# SAM4S_Piezo_LED.net
KiCad netlist of a schematic drawn in Altium Designer
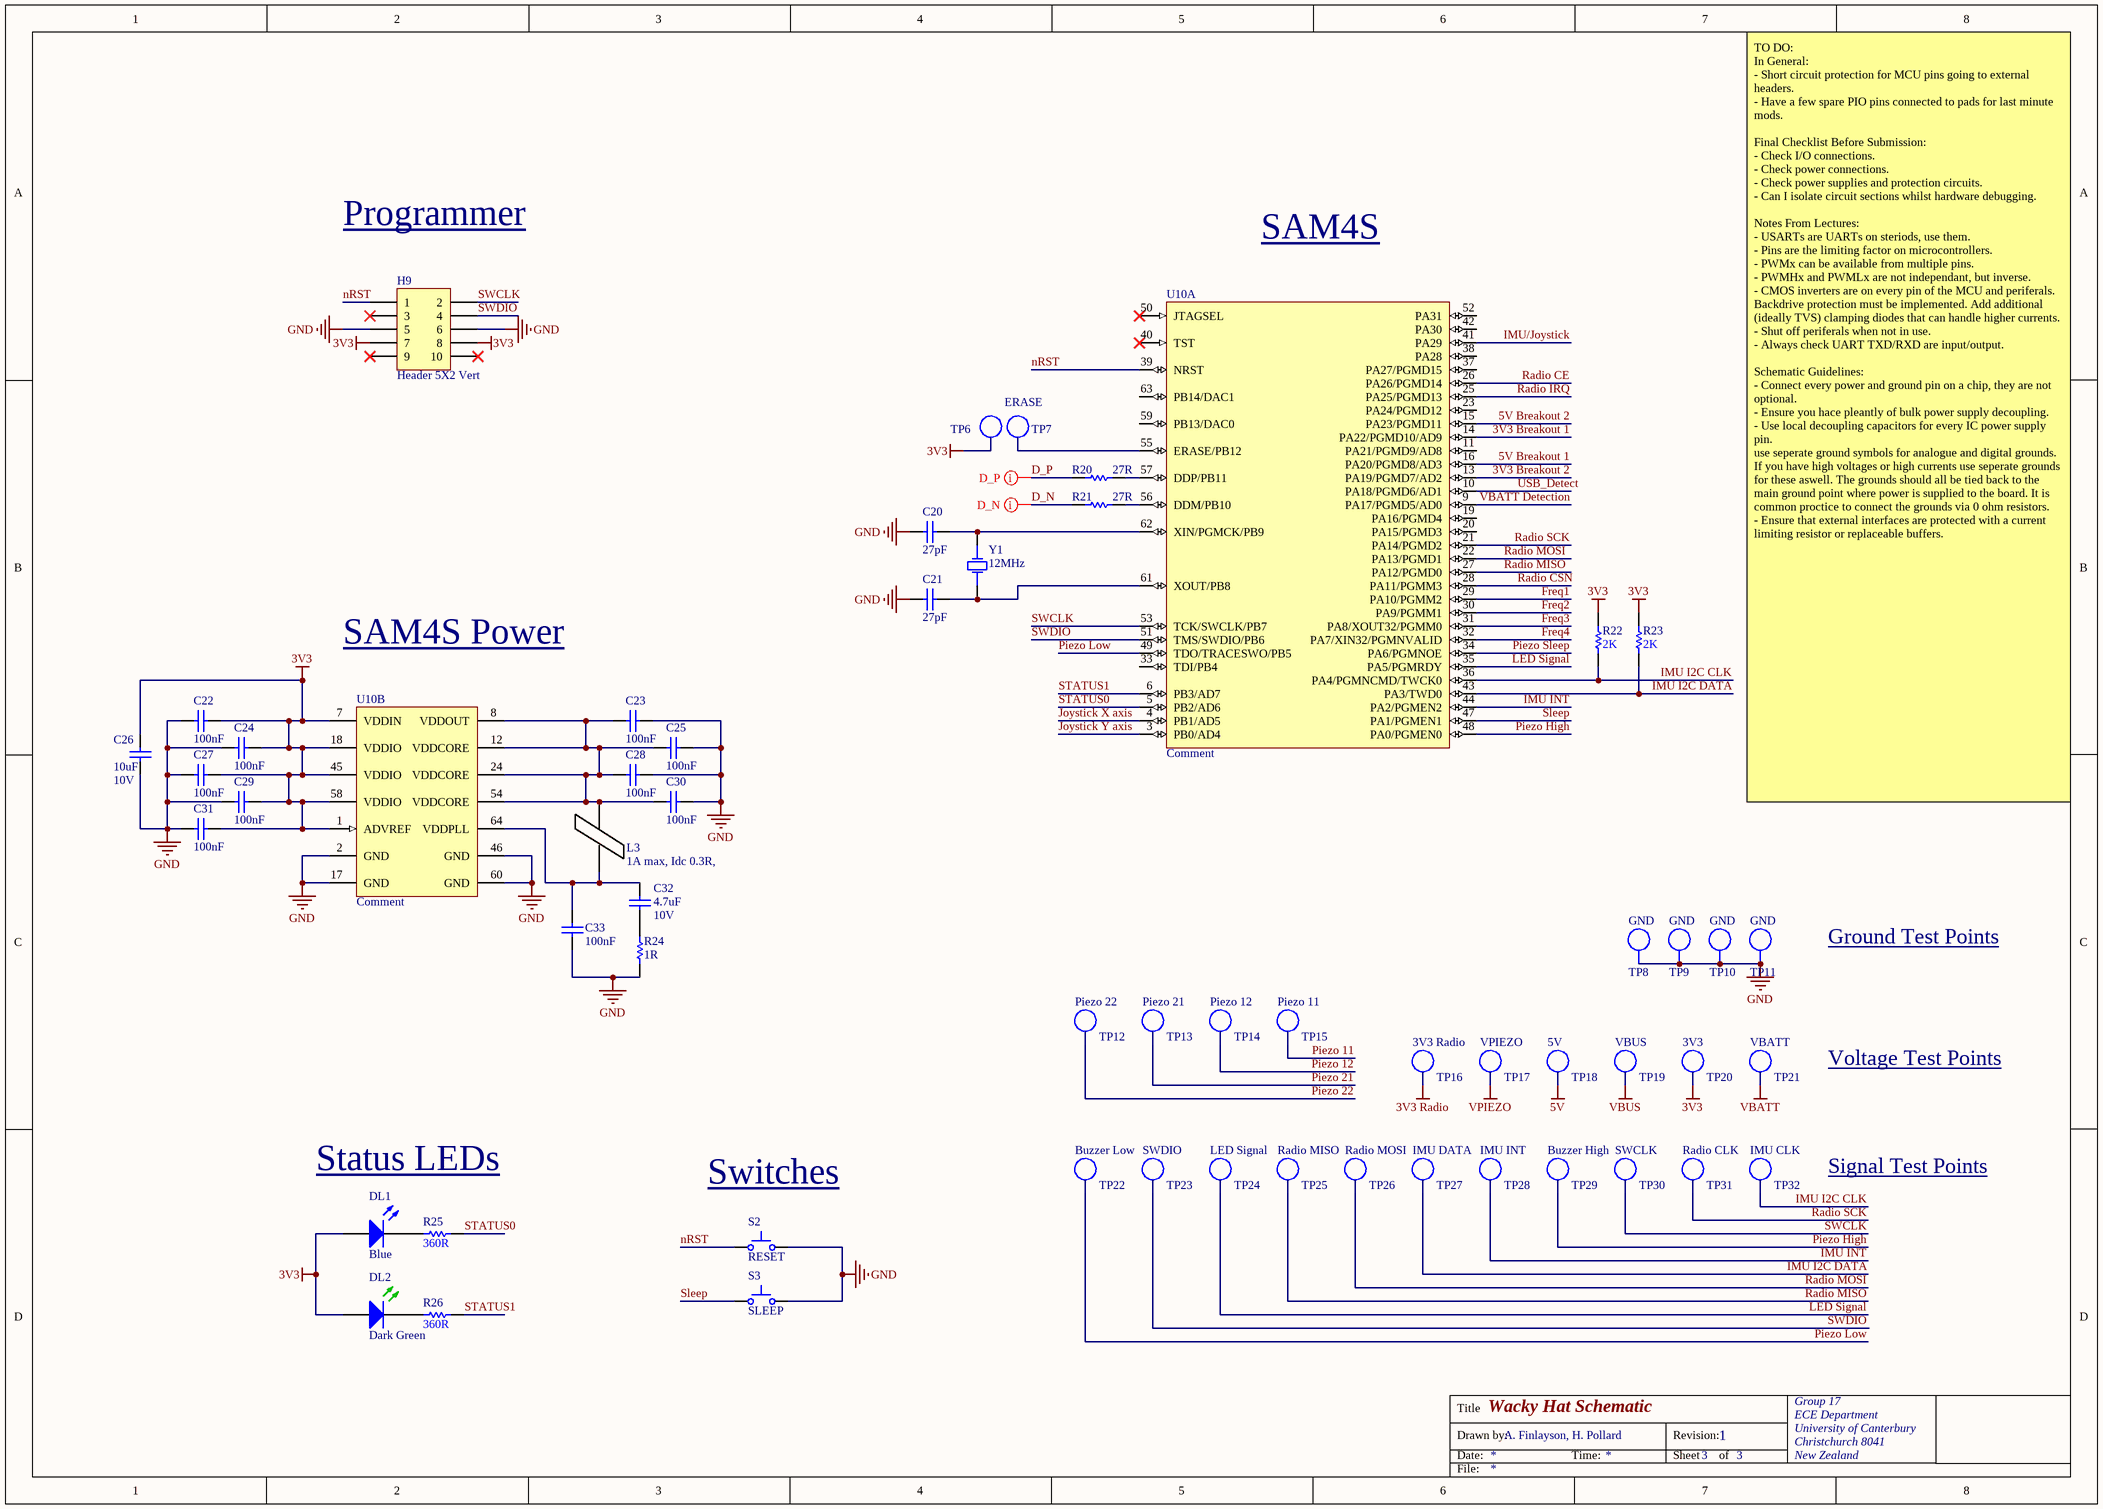
[diagram p0: SAM4S_Piezo_LED.SchDoc]

(export (version "E")
  (design (tool "Eeschema 10.0.6"))
  (components
    (comp (ref "C20")
      (value "27pF")
      (footprint "CAPC1608L")
      (description "CAP CER 27pF NPO/COG +-5% 50V 0603")
      (libsource (lib "ECE AD19Components_19V1") (part "CC_27pF_0603"))
    )
    (comp (ref "C21")
      (value "27pF")
      (footprint "CAPC1608L")
      (description "CAP CER 27pF NPO/COG +-5% 50V 0603")
      (libsource (lib "ECE AD19Components_19V1") (part "CC_27pF_0603"))
    )
    (comp (ref "C22")
      (value "100nF")
      (footprint "CAPC1608L")
      (description "CAP CER 100nF X7R +-10% 50V 0603")
      (libsource (lib "ECE AD19Components_19V1") (part "CC_100nF_0603"))
    )
    (comp (ref "C23")
      (value "100nF")
      (footprint "CAPC1608L")
      (description "CAP CER 100nF X7R +-10% 50V 0603")
      (libsource (lib "ECE AD19Components_19V1") (part "CC_100nF_0603"))
    )
    (comp (ref "C24")
      (value "100nF")
      (footprint "CAPC1608L")
      (description "CAP CER 100nF X7R +-10% 50V 0603")
      (libsource (lib "ECE AD19Components_19V1") (part "CC_100nF_0603"))
    )
    (comp (ref "C25")
      (value "100nF")
      (footprint "CAPC1608L")
      (description "CAP CER 100nF X7R +-10% 50V 0603")
      (libsource (lib "ECE AD19Components_19V1") (part "CC_100nF_0603"))
    )
    (comp (ref "C26")
      (value "10uF")
      (footprint "CAPC2012L")
      (description "CAP CER 10uF X7R +-20% 10V 0805")
      (fields (field (name "MAX VOLTAGE") "10V"))
      (libsource (lib "ECE AD19Components_19V1") (part "CC_10uF_0805_10V"))
    )
    (comp (ref "C27")
      (value "100nF")
      (footprint "CAPC1608L")
      (description "CAP CER 100nF X7R +-10% 50V 0603")
      (libsource (lib "ECE AD19Components_19V1") (part "CC_100nF_0603"))
    )
    (comp (ref "C28")
      (value "100nF")
      (footprint "CAPC1608L")
      (description "CAP CER 100nF X7R +-10% 50V 0603")
      (libsource (lib "ECE AD19Components_19V1") (part "CC_100nF_0603"))
    )
    (comp (ref "C29")
      (value "100nF")
      (footprint "CAPC1608L")
      (description "CAP CER 100nF X7R +-10% 50V 0603")
      (libsource (lib "ECE AD19Components_19V1") (part "CC_100nF_0603"))
    )
    (comp (ref "C30")
      (value "100nF")
      (footprint "CAPC1608L")
      (description "CAP CER 100nF X7R +-10% 50V 0603")
      (libsource (lib "ECE AD19Components_19V1") (part "CC_100nF_0603"))
    )
    (comp (ref "C31")
      (value "100nF")
      (footprint "CAPC1608L")
      (description "CAP CER 100nF X7R +-10% 50V 0603")
      (libsource (lib "ECE AD19Components_19V1") (part "CC_100nF_0603"))
    )
    (comp (ref "C32")
      (value "4.7uF")
      (footprint "CAPC1608N")
      (description "CAP CER 4.7uF X5R +-20%  10V 0603")
      (fields (field (name "MAX VOLTAGE") "10V"))
      (libsource (lib "ECE AD19Components_19V1") (part "CC_4.7uF_0603"))
    )
    (comp (ref "C33")
      (value "100nF")
      (footprint "CAPC1608L")
      (description "CAP CER 100nF X7R +-10% 50V 0603")
      (libsource (lib "ECE AD19Components_19V1") (part "CC_100nF_0603"))
    )
    (comp (ref "DL1")
      (value "Blue")
      (footprint "WL-SMCW0603")
      (description "LED Blue 270mcd 0603 SMD")
      (fields
        (field (name "MANUFACTURER") "WURTH ELEKTRONIK")
        (field (name "MANUFACTURER PART NUMBER") "150060BS75000")
        (field (name "LED COLOUR") "Blue")
      )
      (libsource (lib "ECE AD19Components_19V1") (part "DL_150060BS75000"))
    )
    (comp (ref "DL2")
      (value "Dark Green")
      (footprint "WL-SMCW0603")
      (description "LED Dk Green 430mcd 0603 SMD")
      (fields
        (field (name "MANUFACTURER") "WURTH ELEKTRONIK")
        (field (name "MANUFACTURER PART NUMBER") "150060GS75000")
        (field (name "LED COLOUR") "Dark Green")
      )
      (libsource (lib "ECE AD19Components_19V1") (part "DL_150060GS75000"))
    )
    (comp (ref "H9")
      (value "Header 5X2 Vert")
      (footprint "IDC2.54-V10D")
      (description "IDC Header, 2,54mm, 10-Pin, Vert")
      (libsource (lib "ECE AD19Components_19V1") (part "JA_HDR_IDC_5X2_VERT"))
    )
    (comp (ref "L3")
      (value "1A max, Idc 0.3R,")
      (footprint "INDC3216L")
      (description "Ferrite Bead, Rdc 0.3R, Z100MHZ 600R, Imax 1A, SMD 1206")
      (fields
        (field (name "MANUFACTURER") "FAIR-RITE")
        (field (name "MANUFACTURER PART NUMBER") "2512066017Y1")
      )
      (libsource (lib "ECE AD19Components_19V1") (part "IN_Ferrite-Bead"))
    )
    (comp (ref "R20")
      (value "27R")
      (footprint "RESC1608L")
      (description "RES 27 OHM 1/10W 5% 0603 SMD")
      (libsource (lib "ECE AD19Components_19V1") (part "RS_27R"))
    )
    (comp (ref "R21")
      (value "27R")
      (footprint "RESC1608L")
      (description "RES 27 OHM 1/10W 5% 0603 SMD")
      (libsource (lib "ECE AD19Components_19V1") (part "RS_27R"))
    )
    (comp (ref "R22")
      (value "2K")
      (footprint "RESC1608L")
      (description "RES 2K OHM 1/10W 5% 0603 SMD")
      (libsource (lib "ECE AD19Components_19V1") (part "RS_2K"))
    )
    (comp (ref "R23")
      (value "2K")
      (footprint "RESC1608L")
      (description "RES 2K OHM 1/10W 5% 0603 SMD")
      (libsource (lib "ECE AD19Components_19V1") (part "RS_2K"))
    )
    (comp (ref "R24")
      (value "1R")
      (footprint "RESC3216L")
      (description "RES 1R OHM 1/4W 5% 1206 SMD")
      (libsource (lib "ECE AD19Components_19V1") (part "RT_1R"))
    )
    (comp (ref "R25")
      (value "360R")
      (footprint "RESC1608L")
      (description "RES 360 OHM 1/10W 5% 0603 SMD")
      (libsource (lib "ECE AD19Components_19V1") (part "RS_360R"))
    )
    (comp (ref "R26")
      (value "360R")
      (footprint "RESC1608L")
      (description "RES 360 OHM 1/10W 5% 0603 SMD")
      (libsource (lib "ECE AD19Components_19V1") (part "RS_360R"))
    )
    (comp (ref "S2")
      (value "RESET")
      (footprint "EVQPNF05M")
      (description "Panasonic 6 x 3.5mm SMD Light Touch Switch Type SMD")
      (fields (field (name "MANUFACTURER") "Panasonic"))
      (libsource (lib "ECE AD19Components_19V1") (part "WS_EVQPNF05M"))
    )
    (comp (ref "S3")
      (value "SLEEP")
      (footprint "EVQPNF05M")
      (description "Panasonic 6 x 3.5mm SMD Light Touch Switch Type SMD")
      (fields (field (name "MANUFACTURER") "Panasonic"))
      (libsource (lib "ECE AD19Components_19V1") (part "WS_EVQPNF05M"))
    )
    (comp (ref "TP6")
      (value "TP_0603")
      (footprint "TP_0603")
      (description "Test Point 1.65X0.9X1.2mm SMD")
      (fields
        (field (name "MANUFACTURER") "TE Connectivity AMP Connectors")
        (field (name "MANUFACTURER PART NUMBER") "1625854-3")
      )
      (libsource (lib "ECE AD19Components_19V1") (part "TP_0603"))
    )
    (comp (ref "TP7")
      (value "ERASE")
      (footprint "TP_0603")
      (description "Test Point 1.65X0.9X1.2mm SMD")
      (fields
        (field (name "MANUFACTURER") "TE Connectivity AMP Connectors")
        (field (name "MANUFACTURER PART NUMBER") "1625854-3")
      )
      (libsource (lib "ECE AD19Components_19V1") (part "TP_0603"))
    )
    (comp (ref "TP8")
      (value "GND")
      (footprint "TP_1206")
      (description "Test-Point 3.3x1.6x2.1mm SMD")
      (fields
        (field (name "MANUFACTURER") "Harwin Inc")
        (field (name "MANUFACTURER PART NUMBER") "S1751-46R")
      )
      (libsource (lib "ECE AD19Components_19V1") (part "TP_1206"))
    )
    (comp (ref "TP9")
      (value "GND")
      (footprint "TP_1206")
      (description "Test-Point 3.3x1.6x2.1mm SMD")
      (fields
        (field (name "MANUFACTURER") "Harwin Inc")
        (field (name "MANUFACTURER PART NUMBER") "S1751-46R")
      )
      (libsource (lib "ECE AD19Components_19V1") (part "TP_1206"))
    )
    (comp (ref "TP10")
      (value "GND")
      (footprint "TP_1206")
      (description "Test-Point 3.3x1.6x2.1mm SMD")
      (fields
        (field (name "MANUFACTURER") "Harwin Inc")
        (field (name "MANUFACTURER PART NUMBER") "S1751-46R")
      )
      (libsource (lib "ECE AD19Components_19V1") (part "TP_1206"))
    )
    (comp (ref "TP11")
      (value "GND")
      (footprint "TP_1206")
      (description "Test-Point 3.3x1.6x2.1mm SMD")
      (fields
        (field (name "MANUFACTURER") "Harwin Inc")
        (field (name "MANUFACTURER PART NUMBER") "S1751-46R")
      )
      (libsource (lib "ECE AD19Components_19V1") (part "TP_1206"))
    )
    (comp (ref "TP12")
      (value "Piezo 22")
      (footprint "TP_0603")
      (description "Test Point 1.65X0.9X1.2mm SMD")
      (fields
        (field (name "MANUFACTURER") "TE Connectivity AMP Connectors")
        (field (name "MANUFACTURER PART NUMBER") "1625854-3")
      )
      (libsource (lib "ECE AD19Components_19V1") (part "TP_0603"))
    )
    (comp (ref "TP13")
      (value "Piezo 21")
      (footprint "TP_0603")
      (description "Test Point 1.65X0.9X1.2mm SMD")
      (fields
        (field (name "MANUFACTURER") "TE Connectivity AMP Connectors")
        (field (name "MANUFACTURER PART NUMBER") "1625854-3")
      )
      (libsource (lib "ECE AD19Components_19V1") (part "TP_0603"))
    )
    (comp (ref "TP14")
      (value "Piezo 12")
      (footprint "TP_0603")
      (description "Test Point 1.65X0.9X1.2mm SMD")
      (fields
        (field (name "MANUFACTURER") "TE Connectivity AMP Connectors")
        (field (name "MANUFACTURER PART NUMBER") "1625854-3")
      )
      (libsource (lib "ECE AD19Components_19V1") (part "TP_0603"))
    )
    (comp (ref "TP15")
      (value "Piezo 11")
      (footprint "TP_0603")
      (description "Test Point 1.65X0.9X1.2mm SMD")
      (fields
        (field (name "MANUFACTURER") "TE Connectivity AMP Connectors")
        (field (name "MANUFACTURER PART NUMBER") "1625854-3")
      )
      (libsource (lib "ECE AD19Components_19V1") (part "TP_0603"))
    )
    (comp (ref "TP16")
      (value "3V3 Radio")
      (footprint "TP_0603")
      (description "Test Point 1.65X0.9X1.2mm SMD")
      (fields
        (field (name "MANUFACTURER") "TE Connectivity AMP Connectors")
        (field (name "MANUFACTURER PART NUMBER") "1625854-3")
      )
      (libsource (lib "ECE AD19Components_19V1") (part "TP_0603"))
    )
    (comp (ref "TP17")
      (value "VPIEZO")
      (footprint "TP_0603")
      (description "Test Point 1.65X0.9X1.2mm SMD")
      (fields
        (field (name "MANUFACTURER") "TE Connectivity AMP Connectors")
        (field (name "MANUFACTURER PART NUMBER") "1625854-3")
      )
      (libsource (lib "ECE AD19Components_19V1") (part "TP_0603"))
    )
    (comp (ref "TP18")
      (value "5V")
      (footprint "TP_0603")
      (description "Test Point 1.65X0.9X1.2mm SMD")
      (fields
        (field (name "MANUFACTURER") "TE Connectivity AMP Connectors")
        (field (name "MANUFACTURER PART NUMBER") "1625854-3")
      )
      (libsource (lib "ECE AD19Components_19V1") (part "TP_0603"))
    )
    (comp (ref "TP19")
      (value "VBUS")
      (footprint "TP_0603")
      (description "Test Point 1.65X0.9X1.2mm SMD")
      (fields
        (field (name "MANUFACTURER") "TE Connectivity AMP Connectors")
        (field (name "MANUFACTURER PART NUMBER") "1625854-3")
      )
      (libsource (lib "ECE AD19Components_19V1") (part "TP_0603"))
    )
    (comp (ref "TP20")
      (value "3V3")
      (footprint "TP_0603")
      (description "Test Point 1.65X0.9X1.2mm SMD")
      (fields
        (field (name "MANUFACTURER") "TE Connectivity AMP Connectors")
        (field (name "MANUFACTURER PART NUMBER") "1625854-3")
      )
      (libsource (lib "ECE AD19Components_19V1") (part "TP_0603"))
    )
    (comp (ref "TP21")
      (value "VBATT")
      (footprint "TP_0603")
      (description "Test Point 1.65X0.9X1.2mm SMD")
      (fields
        (field (name "MANUFACTURER") "TE Connectivity AMP Connectors")
        (field (name "MANUFACTURER PART NUMBER") "1625854-3")
      )
      (libsource (lib "ECE AD19Components_19V1") (part "TP_0603"))
    )
    (comp (ref "TP22")
      (value "Buzzer Low")
      (footprint "TP_0603")
      (description "Test Point 1.65X0.9X1.2mm SMD")
      (fields
        (field (name "MANUFACTURER") "TE Connectivity AMP Connectors")
        (field (name "MANUFACTURER PART NUMBER") "1625854-3")
      )
      (libsource (lib "ECE AD19Components_19V1") (part "TP_0603"))
    )
    (comp (ref "TP23")
      (value "SWDIO")
      (footprint "TP_0603")
      (description "Test Point 1.65X0.9X1.2mm SMD")
      (fields
        (field (name "MANUFACTURER") "TE Connectivity AMP Connectors")
        (field (name "MANUFACTURER PART NUMBER") "1625854-3")
      )
      (libsource (lib "ECE AD19Components_19V1") (part "TP_0603"))
    )
    (comp (ref "TP24")
      (value "LED Signal")
      (footprint "TP_0603")
      (description "Test Point 1.65X0.9X1.2mm SMD")
      (fields
        (field (name "MANUFACTURER") "TE Connectivity AMP Connectors")
        (field (name "MANUFACTURER PART NUMBER") "1625854-3")
      )
      (libsource (lib "ECE AD19Components_19V1") (part "TP_0603"))
    )
    (comp (ref "TP25")
      (value "Radio MISO")
      (footprint "TP_0603")
      (description "Test Point 1.65X0.9X1.2mm SMD")
      (fields
        (field (name "MANUFACTURER") "TE Connectivity AMP Connectors")
        (field (name "MANUFACTURER PART NUMBER") "1625854-3")
      )
      (libsource (lib "ECE AD19Components_19V1") (part "TP_0603"))
    )
    (comp (ref "TP26")
      (value "Radio MOSI")
      (footprint "TP_0603")
      (description "Test Point 1.65X0.9X1.2mm SMD")
      (fields
        (field (name "MANUFACTURER") "TE Connectivity AMP Connectors")
        (field (name "MANUFACTURER PART NUMBER") "1625854-3")
      )
      (libsource (lib "ECE AD19Components_19V1") (part "TP_0603"))
    )
    (comp (ref "TP27")
      (value "IMU DATA")
      (footprint "TP_0603")
      (description "Test Point 1.65X0.9X1.2mm SMD")
      (fields
        (field (name "MANUFACTURER") "TE Connectivity AMP Connectors")
        (field (name "MANUFACTURER PART NUMBER") "1625854-3")
      )
      (libsource (lib "ECE AD19Components_19V1") (part "TP_0603"))
    )
    (comp (ref "TP28")
      (value "IMU INT")
      (footprint "TP_0603")
      (description "Test Point 1.65X0.9X1.2mm SMD")
      (fields
        (field (name "MANUFACTURER") "TE Connectivity AMP Connectors")
        (field (name "MANUFACTURER PART NUMBER") "1625854-3")
      )
      (libsource (lib "ECE AD19Components_19V1") (part "TP_0603"))
    )
    (comp (ref "TP29")
      (value "Buzzer High")
      (footprint "TP_0603")
      (description "Test Point 1.65X0.9X1.2mm SMD")
      (fields
        (field (name "MANUFACTURER") "TE Connectivity AMP Connectors")
        (field (name "MANUFACTURER PART NUMBER") "1625854-3")
      )
      (libsource (lib "ECE AD19Components_19V1") (part "TP_0603"))
    )
    (comp (ref "TP30")
      (value "SWCLK")
      (footprint "TP_0603")
      (description "Test Point 1.65X0.9X1.2mm SMD")
      (fields
        (field (name "MANUFACTURER") "TE Connectivity AMP Connectors")
        (field (name "MANUFACTURER PART NUMBER") "1625854-3")
      )
      (libsource (lib "ECE AD19Components_19V1") (part "TP_0603"))
    )
    (comp (ref "TP31")
      (value "Radio CLK")
      (footprint "TP_0603")
      (description "Test Point 1.65X0.9X1.2mm SMD")
      (fields
        (field (name "MANUFACTURER") "TE Connectivity AMP Connectors")
        (field (name "MANUFACTURER PART NUMBER") "1625854-3")
      )
      (libsource (lib "ECE AD19Components_19V1") (part "TP_0603"))
    )
    (comp (ref "TP32")
      (value "IMU CLK")
      (footprint "TP_0603")
      (description "Test Point 1.65X0.9X1.2mm SMD")
      (fields
        (field (name "MANUFACTURER") "TE Connectivity AMP Connectors")
        (field (name "MANUFACTURER PART NUMBER") "1625854-3")
      )
      (libsource (lib "ECE AD19Components_19V1") (part "TP_0603"))
    )
    (comp (ref "U10")
      (value "Comment")
      (footprint "LQFP64_L")
      (description "IC MCU 32BIT 512KB FLASH 64LQFP")
      (fields
        (field (name "MANUFACTURER") "Atmel")
        (field (name "MANUFACTURER PART NUMBER") "ATSAM4S8BA-ANR")
      )
      (libsource (lib "ECE AD19Components_19V1") (part "SE_ATSAM4S16BA-MU"))
    )
    (comp (ref "Y1")
      (value "12MHz")
      (footprint "6.0X3.5-4")
      (description "CRYSTAL 12MHZ 18PF 6X3.5mm SMD")
      (fields
        (field (name "MANUFACTURER") "CTS-Frequency Controls")
        (field (name "MANUFACTURER PART NUMBER") "406C35D12M00000")
        (field (name "FREQUENCY") "12MHz")
      )
      (libsource (lib "ECE AD19Components_19V1") (part "XT_CRYSTAL_12MHz_18pF"))
    )
  )
  (nets
    (net (code "1") (name "/3V3 Breakout 1") (class "Default")
      (node (ref "U10") (pin "14") (pinfunction "PA22/PGMD10/AD9_14") (pintype "bidirectional"))
    )
    (net (code "2") (name "/3V3 Breakout 2") (class "Default")
      (node (ref "U10") (pin "13") (pinfunction "PA19/PGMD7/AD2_13") (pintype "bidirectional"))
    )
    (net (code "3") (name "/5V Breakout 1") (class "Default")
      (node (ref "U10") (pin "16") (pinfunction "PA20/PGMD8/AD3_16") (pintype "bidirectional"))
    )
    (net (code "4") (name "/5V Breakout 2") (class "Default")
      (node (ref "U10") (pin "15") (pinfunction "PA23/PGMD11_15") (pintype "bidirectional"))
    )
    (net (code "5") (name "/D_N") (class "Default")
      (node (ref "R21") (pin "1") (pinfunction "1_1") (pintype "passive"))
    )
    (net (code "6") (name "/D_P") (class "Default")
      (node (ref "R20") (pin "1") (pinfunction "1_1") (pintype "passive"))
    )
    (net (code "7") (name "/Freq1") (class "Default")
      (node (ref "U10") (pin "29") (pinfunction "PA10/PGMM2_29") (pintype "bidirectional"))
    )
    (net (code "8") (name "/Freq2") (class "Default")
      (node (ref "U10") (pin "30") (pinfunction "PA9/PGMM1_30") (pintype "bidirectional"))
    )
    (net (code "9") (name "/Freq3") (class "Default")
      (node (ref "U10") (pin "31") (pinfunction "PA8/XOUT32/PGMM0_31") (pintype "bidirectional"))
    )
    (net (code "10") (name "/Freq4") (class "Default")
      (node (ref "U10") (pin "32") (pinfunction "PA7/XIN32/PGMNVALID_32") (pintype "bidirectional"))
    )
    (net (code "11") (name "/IMU I2C CLK") (class "Default")
      (node (ref "R22") (pin "1") (pinfunction "1_1") (pintype "passive"))
      (node (ref "TP32") (pin "1") (pinfunction "TP_1") (pintype "passive"))
      (node (ref "U10") (pin "36") (pinfunction "PA4/PGMNCMD/TWCK0_36") (pintype "bidirectional"))
    )
    (net (code "12") (name "/IMU I2C DATA") (class "Default")
      (node (ref "R23") (pin "1") (pinfunction "1_1") (pintype "passive"))
      (node (ref "TP27") (pin "1") (pinfunction "TP_1") (pintype "passive"))
      (node (ref "U10") (pin "43") (pinfunction "PA3/TWD0_43") (pintype "bidirectional"))
    )
    (net (code "13") (name "/IMU INT") (class "Default")
      (node (ref "TP28") (pin "1") (pinfunction "TP_1") (pintype "passive"))
      (node (ref "U10") (pin "44") (pinfunction "PA2/PGMEN2_44") (pintype "bidirectional"))
    )
    (net (code "14") (name "/IMU{slash}Joystick") (class "Default")
      (node (ref "U10") (pin "41") (pinfunction "PA29_41") (pintype "bidirectional"))
    )
    (net (code "15") (name "/Joystick X axis") (class "Default")
      (node (ref "U10") (pin "4") (pinfunction "PB1/AD5_4") (pintype "bidirectional"))
    )
    (net (code "16") (name "/Joystick Y axis") (class "Default")
      (node (ref "U10") (pin "3") (pinfunction "PB0/AD4_3") (pintype "bidirectional"))
    )
    (net (code "17") (name "/LED Signal") (class "Default")
      (node (ref "TP24") (pin "1") (pinfunction "TP_1") (pintype "passive"))
      (node (ref "U10") (pin "35") (pinfunction "PA5/PGMRDY_35") (pintype "bidirectional"))
    )
    (net (code "18") (name "/Piezo 11") (class "Default")
      (node (ref "TP15") (pin "1") (pinfunction "TP_1") (pintype "passive"))
    )
    (net (code "19") (name "/Piezo 12") (class "Default")
      (node (ref "TP14") (pin "1") (pinfunction "TP_1") (pintype "passive"))
    )
    (net (code "20") (name "/Piezo 21") (class "Default")
      (node (ref "TP13") (pin "1") (pinfunction "TP_1") (pintype "passive"))
    )
    (net (code "21") (name "/Piezo 22") (class "Default")
      (node (ref "TP12") (pin "1") (pinfunction "TP_1") (pintype "passive"))
    )
    (net (code "22") (name "/Piezo High") (class "Default")
      (node (ref "TP29") (pin "1") (pinfunction "TP_1") (pintype "passive"))
      (node (ref "U10") (pin "48") (pinfunction "PA0/PGMEN0_48") (pintype "bidirectional"))
    )
    (net (code "23") (name "/Piezo Low") (class "Default")
      (node (ref "TP22") (pin "1") (pinfunction "TP_1") (pintype "passive"))
      (node (ref "U10") (pin "49") (pinfunction "TDO/TRACESWO/PB5_49") (pintype "bidirectional"))
    )
    (net (code "24") (name "/Piezo Sleep") (class "Default")
      (node (ref "U10") (pin "34") (pinfunction "PA6/PGMNOE_34") (pintype "bidirectional"))
    )
    (net (code "25") (name "/Radio CE") (class "Default")
      (node (ref "U10") (pin "26") (pinfunction "PA26/PGMD14_26") (pintype "bidirectional"))
    )
    (net (code "26") (name "/Radio CSN") (class "Default")
      (node (ref "U10") (pin "28") (pinfunction "PA11/PGMM3_28") (pintype "bidirectional"))
    )
    (net (code "27") (name "/Radio IRQ") (class "Default")
      (node (ref "U10") (pin "25") (pinfunction "PA25/PGMD13_25") (pintype "bidirectional"))
    )
    (net (code "28") (name "/Radio MISO") (class "Default")
      (node (ref "TP25") (pin "1") (pinfunction "TP_1") (pintype "passive"))
      (node (ref "U10") (pin "27") (pinfunction "PA12/PGMD0_27") (pintype "bidirectional"))
    )
    (net (code "29") (name "/Radio MOSI") (class "Default")
      (node (ref "TP26") (pin "1") (pinfunction "TP_1") (pintype "passive"))
      (node (ref "U10") (pin "22") (pinfunction "PA13/PGMD1_22") (pintype "bidirectional"))
    )
    (net (code "30") (name "/Radio SCK") (class "Default")
      (node (ref "TP31") (pin "1") (pinfunction "TP_1") (pintype "passive"))
      (node (ref "U10") (pin "21") (pinfunction "PA14/PGMD2_21") (pintype "bidirectional"))
    )
    (net (code "31") (name "/STATUS0") (class "Default")
      (node (ref "R25") (pin "2") (pinfunction "2_2") (pintype "passive"))
      (node (ref "U10") (pin "5") (pinfunction "PB2/AD6_5") (pintype "bidirectional"))
    )
    (net (code "32") (name "/STATUS1") (class "Default")
      (node (ref "R26") (pin "2") (pinfunction "2_2") (pintype "passive"))
      (node (ref "U10") (pin "6") (pinfunction "PB3/AD7_6") (pintype "bidirectional"))
    )
    (net (code "33") (name "/SWCLK") (class "Default")
      (node (ref "H9") (pin "2") (pinfunction "2_2") (pintype "passive"))
      (node (ref "TP30") (pin "1") (pinfunction "TP_1") (pintype "passive"))
      (node (ref "U10") (pin "53") (pinfunction "TCK/SWCLK/PB7_53") (pintype "bidirectional"))
    )
    (net (code "34") (name "/SWDIO") (class "Default")
      (node (ref "H9") (pin "4") (pinfunction "4_4") (pintype "passive"))
      (node (ref "TP23") (pin "1") (pinfunction "TP_1") (pintype "passive"))
      (node (ref "U10") (pin "51") (pinfunction "TMS/SWDIO/PB6_51") (pintype "bidirectional"))
    )
    (net (code "35") (name "/Sleep") (class "Default")
      (node (ref "S3") (pin "1") (pintype "passive"))
      (node (ref "U10") (pin "47") (pinfunction "PA1/PGMEN1_47") (pintype "bidirectional"))
    )
    (net (code "36") (name "/USB_Detect") (class "Default")
      (node (ref "U10") (pin "10") (pinfunction "PA18/PGMD6/AD1_10") (pintype "bidirectional"))
    )
    (net (code "37") (name "/VBATT Detection") (class "Default")
      (node (ref "U10") (pin "9") (pinfunction "PA17/PGMD5/AD0_9") (pintype "bidirectional"))
    )
    (net (code "38") (name "/nRST") (class "Default")
      (node (ref "H9") (pin "1") (pinfunction "1_1") (pintype "passive"))
      (node (ref "S2") (pin "1") (pintype "passive"))
      (node (ref "U10") (pin "39") (pinfunction "NRST_39") (pintype "bidirectional"))
    )
    (net (code "39") (name "3V3") (class "Default")
      (node (ref "C22") (pin "2") (pinfunction "2_2") (pintype "passive"))
      (node (ref "C24") (pin "2") (pinfunction "2_2") (pintype "passive"))
      (node (ref "C26") (pin "2") (pinfunction "2_2") (pintype "passive"))
      (node (ref "C27") (pin "2") (pinfunction "2_2") (pintype "passive"))
      (node (ref "C29") (pin "2") (pinfunction "2_2") (pintype "passive"))
      (node (ref "C31") (pin "2") (pinfunction "2_2") (pintype "passive"))
      (node (ref "DL1") (pin "2") (pinfunction "A_2") (pintype "passive"))
      (node (ref "DL2") (pin "2") (pinfunction "A_2") (pintype "passive"))
      (node (ref "H9") (pin "7") (pinfunction "7_7") (pintype "passive"))
      (node (ref "H9") (pin "8") (pinfunction "8_8") (pintype "passive"))
      (node (ref "R22") (pin "2") (pinfunction "2_2") (pintype "passive"))
      (node (ref "R23") (pin "2") (pinfunction "2_2") (pintype "passive"))
      (node (ref "TP20") (pin "1") (pinfunction "TP_1") (pintype "passive"))
      (node (ref "TP6") (pin "1") (pinfunction "TP_1") (pintype "passive"))
      (node (ref "U10") (pin "1") (pinfunction "ADVREF_1") (pintype "input"))
      (node (ref "U10") (pin "18") (pinfunction "VDDIO_18") (pintype "power_in"))
      (node (ref "U10") (pin "45") (pinfunction "VDDIO_45") (pintype "power_in"))
      (node (ref "U10") (pin "58") (pinfunction "VDDIO_58") (pintype "power_in"))
      (node (ref "U10") (pin "7") (pinfunction "VDDIN_7") (pintype "power_in"))
    )
    (net (code "40") (name "3V3 Radio") (class "Default")
      (node (ref "TP16") (pin "1") (pinfunction "TP_1") (pintype "passive"))
    )
    (net (code "41") (name "5V") (class "Default")
      (node (ref "TP18") (pin "1") (pinfunction "TP_1") (pintype "passive"))
    )
    (net (code "42") (name "GND") (class "Default")
      (node (ref "C20") (pin "1") (pinfunction "1_1") (pintype "passive"))
      (node (ref "C21") (pin "1") (pinfunction "1_1") (pintype "passive"))
      (node (ref "C22") (pin "1") (pinfunction "1_1") (pintype "passive"))
      (node (ref "C23") (pin "2") (pinfunction "2_2") (pintype "passive"))
      (node (ref "C24") (pin "1") (pinfunction "1_1") (pintype "passive"))
      (node (ref "C25") (pin "2") (pinfunction "2_2") (pintype "passive"))
      (node (ref "C26") (pin "1") (pinfunction "1_1") (pintype "passive"))
      (node (ref "C27") (pin "1") (pinfunction "1_1") (pintype "passive"))
      (node (ref "C28") (pin "2") (pinfunction "2_2") (pintype "passive"))
      (node (ref "C29") (pin "1") (pinfunction "1_1") (pintype "passive"))
      (node (ref "C30") (pin "2") (pinfunction "2_2") (pintype "passive"))
      (node (ref "C31") (pin "1") (pinfunction "1_1") (pintype "passive"))
      (node (ref "C33") (pin "1") (pinfunction "1_1") (pintype "passive"))
      (node (ref "H9") (pin "5") (pinfunction "5_5") (pintype "passive"))
      (node (ref "H9") (pin "6") (pinfunction "6_6") (pintype "passive"))
      (node (ref "R24") (pin "1") (pinfunction "1_1") (pintype "passive"))
      (node (ref "S2") (pin "2") (pintype "passive"))
      (node (ref "S3") (pin "2") (pintype "passive"))
      (node (ref "TP10") (pin "1") (pinfunction "1_1") (pintype "passive"))
      (node (ref "TP11") (pin "1") (pinfunction "1_1") (pintype "passive"))
      (node (ref "TP8") (pin "1") (pinfunction "1_1") (pintype "passive"))
      (node (ref "TP9") (pin "1") (pinfunction "1_1") (pintype "passive"))
      (node (ref "U10") (pin "17") (pinfunction "GND_17") (pintype "power_in"))
      (node (ref "U10") (pin "2") (pinfunction "GND_2") (pintype "power_in"))
      (node (ref "U10") (pin "46") (pinfunction "GND_46") (pintype "power_in"))
      (node (ref "U10") (pin "60") (pinfunction "GND_60") (pintype "power_in"))
    )
    (net (code "43") (name "Net-(C32-Pad1)") (class "Default")
      (node (ref "C32") (pin "1") (pinfunction "1_1") (pintype "passive"))
      (node (ref "R24") (pin "2") (pinfunction "2_2") (pintype "passive"))
    )
    (net (code "44") (name "Net-(DL1-K)") (class "Default")
      (node (ref "DL1") (pin "1") (pinfunction "K_1") (pintype "passive"))
      (node (ref "R25") (pin "1") (pinfunction "1_1") (pintype "passive"))
    )
    (net (code "45") (name "Net-(DL2-K)") (class "Default")
      (node (ref "DL2") (pin "1") (pinfunction "K_1") (pintype "passive"))
      (node (ref "R26") (pin "1") (pinfunction "1_1") (pintype "passive"))
    )
    (net (code "46") (name "Net-(TP7-TP)") (class "Default")
      (node (ref "TP7") (pin "1") (pinfunction "TP_1") (pintype "passive"))
      (node (ref "U10") (pin "55") (pinfunction "ERASE/PB12_55") (pintype "bidirectional"))
    )
    (net (code "47") (name "Net-(U10A-DDM{slash}PB10)") (class "Default")
      (node (ref "R21") (pin "2") (pinfunction "2_2") (pintype "passive"))
      (node (ref "U10") (pin "56") (pinfunction "DDM/PB10_56") (pintype "bidirectional"))
    )
    (net (code "48") (name "Net-(U10A-DDP{slash}PB11)") (class "Default")
      (node (ref "R20") (pin "2") (pinfunction "2_2") (pintype "passive"))
      (node (ref "U10") (pin "57") (pinfunction "DDP/PB11_57") (pintype "bidirectional"))
    )
    (net (code "49") (name "Net-(U10A-XIN{slash}PGMCK{slash}PB9)") (class "Default")
      (node (ref "C20") (pin "2") (pinfunction "2_2") (pintype "passive"))
      (node (ref "U10") (pin "62") (pinfunction "XIN/PGMCK/PB9_62") (pintype "bidirectional"))
      (node (ref "Y1") (pin "3") (pinfunction "OSC2_3") (pintype "passive"))
    )
    (net (code "50") (name "Net-(U10A-XOUT{slash}PB8)") (class "Default")
      (node (ref "C21") (pin "2") (pinfunction "2_2") (pintype "passive"))
      (node (ref "U10") (pin "61") (pinfunction "XOUT/PB8_61") (pintype "bidirectional"))
      (node (ref "Y1") (pin "1") (pinfunction "OSC1_1") (pintype "passive"))
    )
    (net (code "51") (name "Net-(U10B-VDDOUT)") (class "Default")
      (node (ref "C23") (pin "1") (pinfunction "1_1") (pintype "passive"))
      (node (ref "C25") (pin "1") (pinfunction "1_1") (pintype "passive"))
      (node (ref "C28") (pin "1") (pinfunction "1_1") (pintype "passive"))
      (node (ref "C30") (pin "1") (pinfunction "1_1") (pintype "passive"))
      (node (ref "L3") (pin "2") (pinfunction "2_2") (pintype "passive"))
      (node (ref "U10") (pin "12") (pinfunction "VDDCORE_12") (pintype "power_in"))
      (node (ref "U10") (pin "24") (pinfunction "VDDCORE_24") (pintype "power_in"))
      (node (ref "U10") (pin "54") (pinfunction "VDDCORE_54") (pintype "power_in"))
      (node (ref "U10") (pin "8") (pinfunction "VDDOUT_8") (pintype "power_in"))
    )
    (net (code "52") (name "Net-(U10B-VDDPLL)") (class "Default")
      (node (ref "C32") (pin "2") (pinfunction "2_2") (pintype "passive"))
      (node (ref "C33") (pin "2") (pinfunction "2_2") (pintype "passive"))
      (node (ref "L3") (pin "1") (pinfunction "1_1") (pintype "passive"))
      (node (ref "U10") (pin "64") (pinfunction "VDDPLL_64") (pintype "power_in"))
    )
    (net (code "53") (name "VBATT") (class "Default")
      (node (ref "TP21") (pin "1") (pinfunction "TP_1") (pintype "passive"))
    )
    (net (code "54") (name "VBUS") (class "Default")
      (node (ref "TP19") (pin "1") (pinfunction "TP_1") (pintype "passive"))
    )
    (net (code "55") (name "VPIEZO") (class "Default")
      (node (ref "TP17") (pin "1") (pinfunction "TP_1") (pintype "passive"))
    )
    (net (code "56") (name "unconnected-(H9-Pad3)") (class "Default")
      (node (ref "H9") (pin "3") (pinfunction "3_3") (pintype "passive+no_connect"))
    )
    (net (code "57") (name "unconnected-(H9-Pad9)") (class "Default")
      (node (ref "H9") (pin "9") (pinfunction "9_9") (pintype "passive+no_connect"))
    )
    (net (code "58") (name "unconnected-(H9-Pad10)") (class "Default")
      (node (ref "H9") (pin "10") (pinfunction "10_10") (pintype "passive+no_connect"))
    )
    (net (code "59") (name "unconnected-(U10A-JTAGSEL-Pad50)") (class "Default")
      (node (ref "U10") (pin "50") (pinfunction "JTAGSEL_50") (pintype "input+no_connect"))
    )
    (net (code "60") (name "unconnected-(U10A-PA15{slash}PGMD3-Pad20)") (class "Default")
      (node (ref "U10") (pin "20") (pinfunction "PA15/PGMD3_20") (pintype "bidirectional"))
    )
    (net (code "61") (name "unconnected-(U10A-PA16{slash}PGMD4-Pad19)") (class "Default")
      (node (ref "U10") (pin "19") (pinfunction "PA16/PGMD4_19") (pintype "bidirectional"))
    )
    (net (code "62") (name "unconnected-(U10A-PA21{slash}PGMD9{slash}AD8-Pad11)") (class "Default")
      (node (ref "U10") (pin "11") (pinfunction "PA21/PGMD9/AD8_11") (pintype "bidirectional"))
    )
    (net (code "63") (name "unconnected-(U10A-PA24{slash}PGMD12-Pad23)") (class "Default")
      (node (ref "U10") (pin "23") (pinfunction "PA24/PGMD12_23") (pintype "bidirectional"))
    )
    (net (code "64") (name "unconnected-(U10A-PA27{slash}PGMD15-Pad37)") (class "Default")
      (node (ref "U10") (pin "37") (pinfunction "PA27/PGMD15_37") (pintype "bidirectional"))
    )
    (net (code "65") (name "unconnected-(U10A-PA28-Pad38)") (class "Default")
      (node (ref "U10") (pin "38") (pinfunction "PA28_38") (pintype "bidirectional"))
    )
    (net (code "66") (name "unconnected-(U10A-PA30-Pad42)") (class "Default")
      (node (ref "U10") (pin "42") (pinfunction "PA30_42") (pintype "bidirectional"))
    )
    (net (code "67") (name "unconnected-(U10A-PA31-Pad52)") (class "Default")
      (node (ref "U10") (pin "52") (pinfunction "PA31_52") (pintype "bidirectional"))
    )
    (net (code "68") (name "unconnected-(U10A-PB13{slash}DAC0-Pad59)") (class "Default")
      (node (ref "U10") (pin "59") (pinfunction "PB13/DAC0_59") (pintype "bidirectional"))
    )
    (net (code "69") (name "unconnected-(U10A-PB14{slash}DAC1-Pad63)") (class "Default")
      (node (ref "U10") (pin "63") (pinfunction "PB14/DAC1_63") (pintype "bidirectional"))
    )
    (net (code "70") (name "unconnected-(U10A-TDI{slash}PB4-Pad33)") (class "Default")
      (node (ref "U10") (pin "33") (pinfunction "TDI/PB4_33") (pintype "bidirectional"))
    )
    (net (code "71") (name "unconnected-(U10A-TST-Pad40)") (class "Default")
      (node (ref "U10") (pin "40") (pinfunction "TST_40") (pintype "input+no_connect"))
    )
  )
)
